# Main_MPPT.net
KiCad netlist of a schematic drawn in Altium Designer
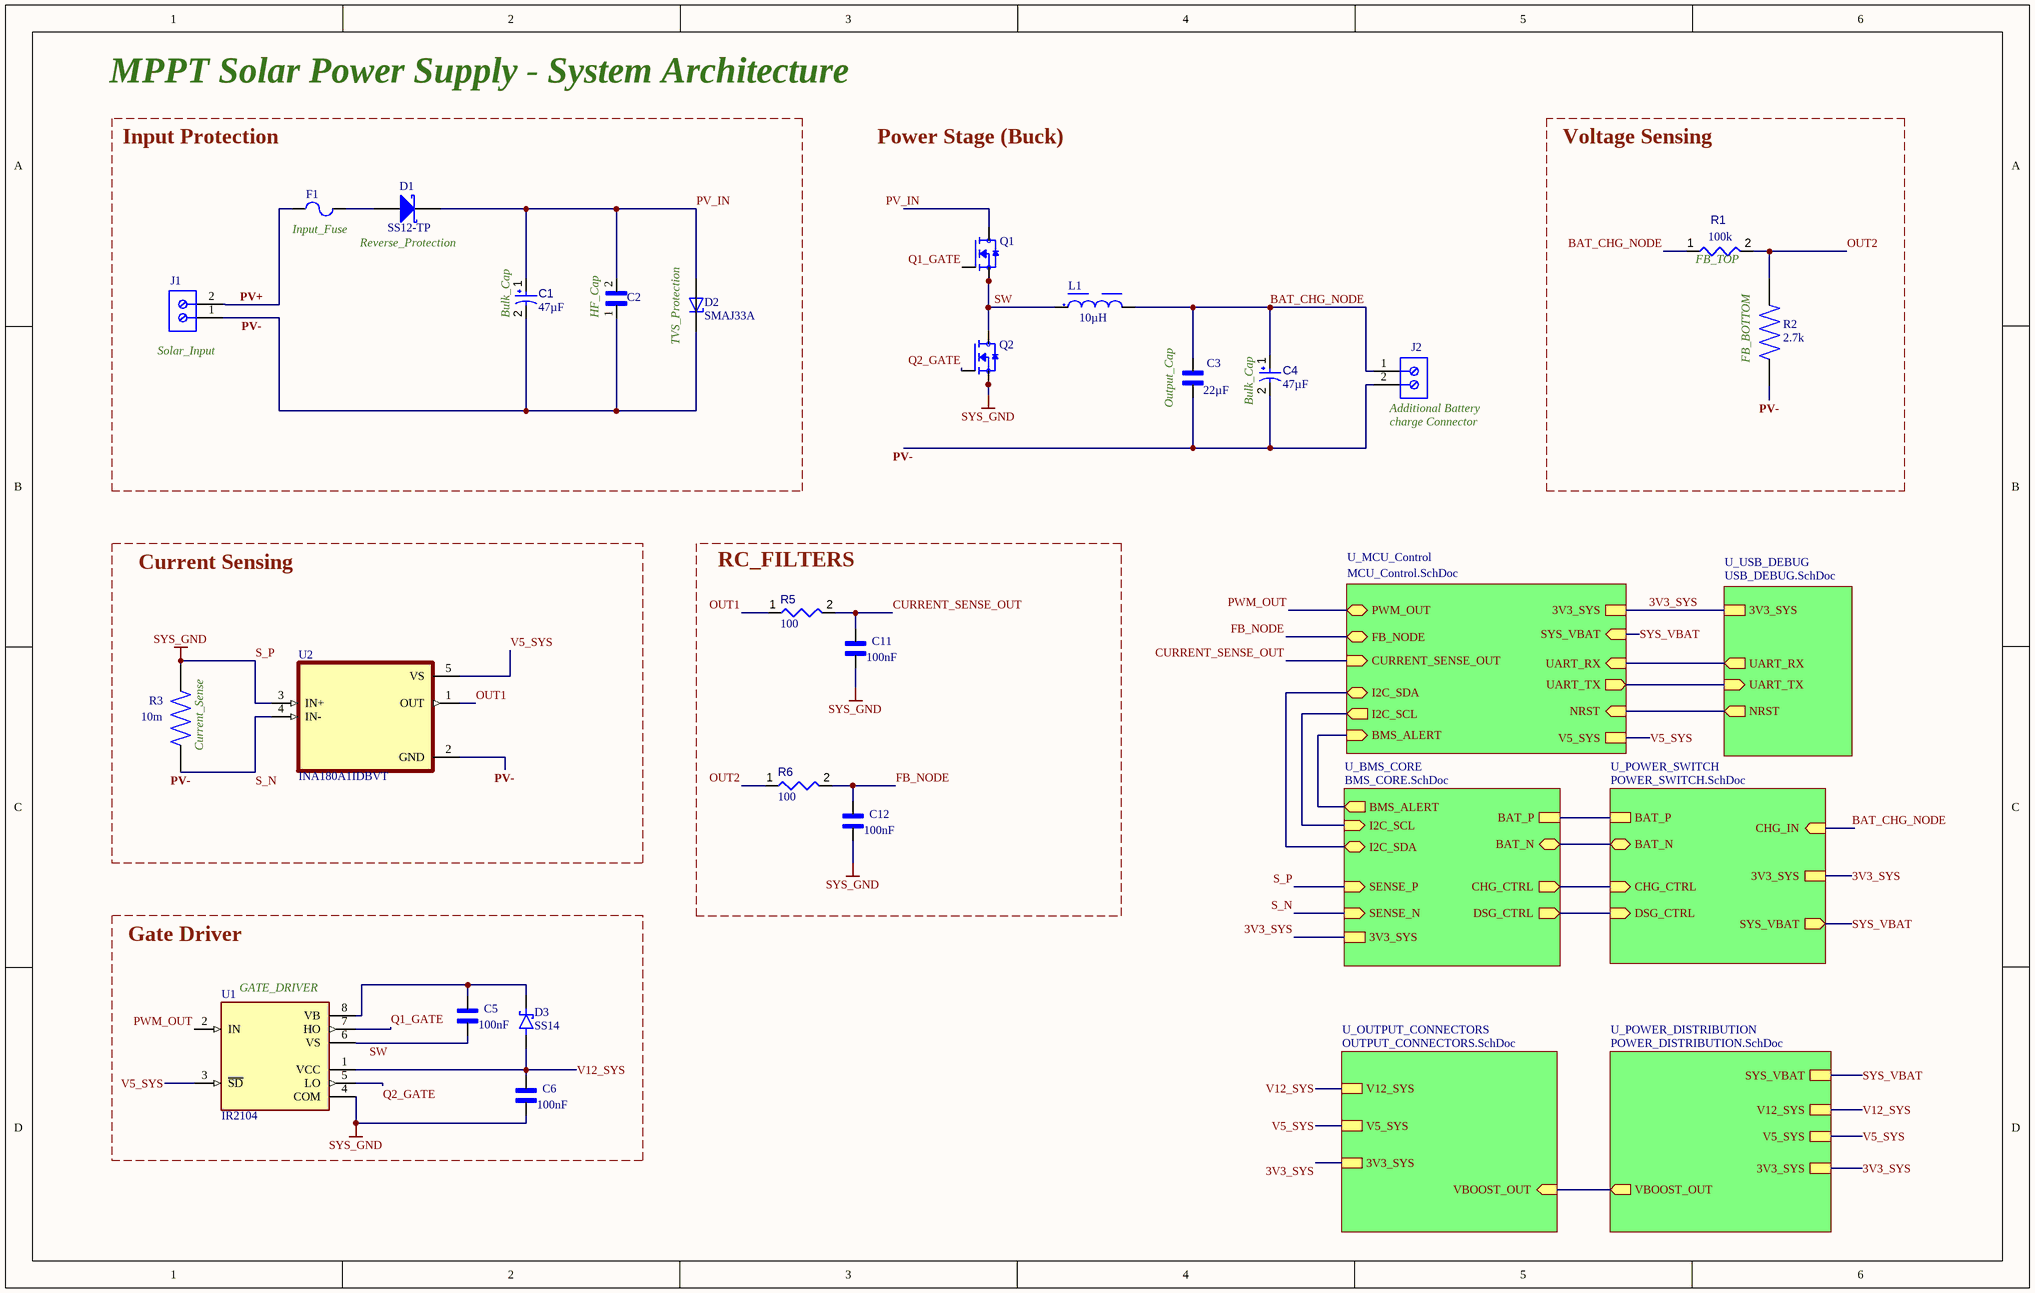
[diagram p0: Main_MPPT.SchDoc]

(export (version "E")
  (design (tool "Eeschema 10.0.6"))
  (components
    (comp (ref "C1")
      (value "47µF")
      (footprint "CAPPR55-250-1120X630X1220")
      (description "Aluminum Electrolytic Capacitor, 47 uF, +/- 20%, 50 V, -40 to 85 degC, 2-Pin THD, RoHS, Bulk")
      (fields (field (name "MANUFACTURER") "Panasonic") (field (name "TOLERANCE") "20%"))
      (libsource (lib "YUKESH S") (part "CAP-P-2"))
    )
    (comp (ref "C2")
      (value "C3216X7R1H106K160AE")
      (footprint "CAPC3216X190N")
      (description "10 ÂµF Â±10% 50V Ceramic Capacitor X7R 1206 (3216 Metric)")
      (fields (field (name "MF") "TDK Corporation"))
      (libsource (lib "C3216X7R1H106K160AE") (part "C3216X7R1H106K160AE"))
    )
    (comp (ref "C3")
      (value "22µF")
      (footprint "CAPC3225X270N")
      (description "SMD capacitor X7R(EIA) with capacitance 22uF Tol.10%. Rated voltage 25Vdc 125C")
      (fields (field (name "MP") "GRM32ER71E226KE15L") (field (name "MF") "Murata Electronics"))
      (libsource (lib "YUKESH S") (part "GRM32ER71E226KE15L"))
    )
    (comp (ref "C4")
      (value "47µF")
      (footprint "CAPPR55-250-1120X630X1220")
      (description "Aluminum Electrolytic Capacitor, 47 uF, +/- 20%, 50 V, -40 to 85 degC, 2-Pin THD, RoHS, Bulk")
      (fields (field (name "MANUFACTURER") "Panasonic") (field (name "TOLERANCE") "20%"))
      (libsource (lib "") (part "CAP-P-2_1"))
    )
    (comp (ref "C5")
      (value "100nF")
      (footprint "CAPC1608X90N")
      (description "Capacitor MLCC 0603 100nF 16V")
      (fields (field (name "MP") "0603YC104KAZ2A") (field (name "MF") "AVX"))
      (libsource (lib "YUKESH S") (part "0603YC104KAZ2A"))
    )
    (comp (ref "C6")
      (value "100nF")
      (footprint "CAPC1608X90N")
      (description "Capacitor MLCC 0603 100nF 16V")
      (fields (field (name "MP") "0603YC104KAZ2A") (field (name "MF") "AVX"))
      (libsource (lib "YUKESH S") (part "0603YC104KAZ2A"))
    )
    (comp (ref "C11")
      (value "100nF")
      (footprint "CAPC1608X90N")
      (description "Capacitor MLCC 0603 100nF 16V")
      (fields (field (name "MP") "0603YC104KAZ2A") (field (name "MF") "AVX"))
      (libsource (lib "YUKESH S") (part "0603YC104KAZ2A"))
    )
    (comp (ref "C12")
      (value "100nF")
      (footprint "CAPC1608X90N")
      (description "Capacitor MLCC 0603 100nF 16V")
      (fields (field (name "MP") "0603YC104KAZ2A") (field (name "MF") "AVX"))
      (libsource (lib "YUKESH S") (part "0603YC104KAZ2A"))
    )
    (comp (ref "D1")
      (value "SS12-TP")
      (footprint "MCC-DO-214AC-2_V")
      (description "Schottky Rectifier, 20 V, 1 A, -55 to 125 degC, 2-Pin DO-214AC, RoHS, Tape and Reel")
      (fields (field (name "MANUFACTURER") "Micro Commercial Components"))
      (libsource (lib "YUKESH S") (part "DSKY-AK-2"))
    )
    (comp (ref "D2")
      (value "SMAJ33A")
      (footprint "Copy of DIOM4325X250N")
      (description "400W, 38.7V, 5%, Unidirectional, TVS")
      (fields (field (name "MF") "Taiwan Semiconductor"))
      (libsource (lib "YUKESH S") (part "SMAJ33A"))
    )
    (comp (ref "D3")
      (value "SS14")
      (footprint "DIOM4325X250N")
      (description "1A, 40V, Schottky Rectifier")
      (fields (field (name "MF") "Taiwan Semiconductor"))
      (libsource (lib "YUKESH S") (part "SS14"))
    )
    (comp (ref "F1")
      (value "0154001.DR")
      (footprint "LFUS-0154001.DR_V")
      (description "Very Fast-Acting Fuse, 1 A, -55 to 125 degC, 2-Pin SMD, RoHS, Tape and Reel")
      (fields (field (name "MANUFACTURER") "Littelfuse"))
      (libsource (lib "Altium Content Vault") (part "FUSE-2"))
    )
    (comp (ref "J1")
      (value "691254810002")
      (footprint "691254810002")
      (description "Terminal Block, 10MM Pitch, Horizontal, Rising Cage Clamp, 12-30 AWG, 2 Pin")
      (libsource (lib "") (part "TBL - 1R - 02P - Screw_1"))
    )
    (comp (ref "J2")
      (value "691254810002")
      (footprint "691254810002")
      (description "Terminal Block, 10MM Pitch, Horizontal, Rising Cage Clamp, 12-30 AWG, 2 Pin")
      (libsource (lib "Altium Content Vault") (part "TBL - 1R - 02P - Screw"))
    )
    (comp (ref "L1")
      (value "10µH")
      (footprint "WE-PD_1260")
      (description "Power inductor SMD WE-PD L 10.0uH 4.09A")
      (fields (field (name "MF") "WÃ¼rth Elektronik") (field (name "MP") "74477110"))
      (libsource (lib "YUKESH S") (part "WE-PD_1260"))
    )
    (comp (ref "Q1")
      (value "CSD18540Q5BT")
      (footprint "TRANS_CSD18540Q5BT")
      (description "60-V, N channel NexFETâ„¢ power MOSFET, single SON 5 mm x 6 mm, 2.2 mOhm")
      (fields (field (name "MF") "Texas Instruments"))
      (libsource (lib "YUKESH S") (part "CSD18540Q5BT"))
    )
    (comp (ref "Q2")
      (value "CSD18540Q5BT")
      (footprint "TRANS_CSD18540Q5BT")
      (description "60-V, N channel NexFETâ„¢ power MOSFET, single SON 5 mm x 6 mm, 2.2 mOhm")
      (fields (field (name "MF") "Texas Instruments"))
      (libsource (lib "YUKESH S") (part "CSD18540Q5BT"))
    )
    (comp (ref "R1")
      (value "100k")
      (footprint "RESC0402(1005)_L")
      (description "100K 0.063W 1% 0402 (1005 Metric)  SMD")
      (fields (field (name "POWER") "63mW") (field (name "TOLERANCE") "1%"))
      (libsource (lib "YUKESH S") (part "100KR2F"))
    )
    (comp (ref "R2")
      (value "2.7k")
      (footprint "RES_ERJ2RHD2702X")
      (description "ERJ2R Resistor 0.063W 27K 0.5% 50ppm")
      (fields (field (name "MF") "Panasonic") (field (name "MP") "ERJ2RHD2702X"))
      (libsource (lib "YUKESH S") (part "ERJ2RHD2702X"))
    )
    (comp (ref "R3")
      (value "10m")
      (footprint "RESC6331X88N")
      (fields (field (name "MP") "WSL2512R0100FEA18") (field (name "MF") "Vishay Intertechnology"))
      (libsource (lib "YUKESH S") (part "WSL2512R0100FEA18"))
    )
    (comp (ref "R5")
      (value "100")
      (footprint "RESC0402(1005)_L")
      (description "100R 0.063W 1% 0402 (1005 Metric)  SMD")
      (fields (field (name "TOLERANCE") "1%") (field (name "POWER") "63mW"))
      (libsource (lib "YUKESH S") (part "100R2F"))
    )
    (comp (ref "R6")
      (value "100")
      (footprint "RESC0402(1005)_L")
      (description "100R 0.063W 1% 0402 (1005 Metric)  SMD")
      (fields (field (name "TOLERANCE") "1%") (field (name "POWER") "63mW"))
      (libsource (lib "YUKESH S") (part "100R2F"))
    )
    (comp (ref "U1")
      (value "IR2104")
      (footprint "DIP762W45P254L988H533Q8")
      (description "Half-Bridge Gate Driver IC Non-Inverting 8-PDIP")
      (fields (field (name "MF") "Infineon Technologies"))
      (libsource (lib "YUKESH S") (part "IR2104"))
    )
    (comp (ref "U2")
      (value "INA180A1IDBVT")
      (footprint "SOT95P280X145-5N")
      (description "26V, 350kHz ì „ë¥˜ ê°ì§€ ì")
      (fields (field (name "MF") "Texas Instruments"))
      (libsource (lib "YUKESH S") (part "INA180A1IDBVT"))
    )
  )
  (nets
    (net (code "2") (name "/BAT_CHG_NODE") (class "Default")
      (node (ref "C3") (pin "2") (pinfunction "2_2") (pintype "passive"))
      (node (ref "C4") (pin "1") (pinfunction "1_1") (pintype "passive"))
      (node (ref "J2") (pin "1") (pinfunction "1_1") (pintype "passive"))
      (node (ref "L1") (pin "2") (pinfunction "2_2") (pintype "passive"))
      (node (ref "R1") (pin "1") (pinfunction "1_1") (pintype "passive"))
    )
    (net (code "7") (name "/CURRENT_SENSE_OUT") (class "Default")
      (node (ref "C11") (pin "2") (pinfunction "2_2") (pintype "passive"))
      (node (ref "R5") (pin "2") (pinfunction "2_2") (pintype "passive"))
    )
    (net (code "9") (name "/FB_NODE") (class "Default")
      (node (ref "C12") (pin "2") (pinfunction "2_2") (pintype "passive"))
      (node (ref "R6") (pin "2") (pinfunction "2_2") (pintype "passive"))
    )
    (net (code "13") (name "/OUT1") (class "Default")
      (node (ref "R5") (pin "1") (pinfunction "1_1") (pintype "passive"))
      (node (ref "U2") (pin "1") (pinfunction "OUT_1") (pintype "output"))
    )
    (net (code "14") (name "/OUT2") (class "Default")
      (node (ref "R1") (pin "2") (pinfunction "2_2") (pintype "passive"))
      (node (ref "R2") (pin "2") (pinfunction "2_2") (pintype "passive"))
      (node (ref "R6") (pin "1") (pinfunction "1_1") (pintype "passive"))
    )
    (net (code "15") (name "/PV+") (class "Default")
      (node (ref "F1") (pin "1") (pinfunction "1_1") (pintype "passive"))
      (node (ref "J1") (pin "2") (pinfunction "2_2") (pintype "passive"))
    )
    (net (code "16") (name "/PV-") (class "Default")
      (node (ref "C1") (pin "2") (pinfunction "2_2") (pintype "passive"))
      (node (ref "C2") (pin "1") (pinfunction "1_1") (pintype "passive"))
      (node (ref "C3") (pin "1") (pinfunction "1_1") (pintype "passive"))
      (node (ref "C4") (pin "2") (pinfunction "2_2") (pintype "passive"))
      (node (ref "D2") (pin "C") (pinfunction "C_C") (pintype "passive"))
      (node (ref "J1") (pin "1") (pinfunction "1_1") (pintype "passive"))
      (node (ref "J2") (pin "2") (pinfunction "2_2") (pintype "passive"))
      (node (ref "R2") (pin "1") (pinfunction "1_1") (pintype "passive"))
      (node (ref "R3") (pin "1") (pinfunction "1_1") (pintype "passive"))
      (node (ref "U2") (pin "2") (pinfunction "GND_2") (pintype "power_in"))
      (node (ref "U2") (pin "4") (pinfunction "IN-_4") (pintype "input"))
    )
    (net (code "17") (name "/PV_IN") (class "Default")
      (node (ref "C1") (pin "1") (pinfunction "1_1") (pintype "passive"))
      (node (ref "C2") (pin "2") (pinfunction "2_2") (pintype "passive"))
      (node (ref "D1") (pin "2") (pinfunction "K_2") (pintype "passive"))
      (node (ref "D2") (pin "A") (pinfunction "A_A") (pintype "passive"))
      (node (ref "Q1") (pin "5_6_7_8") (pinfunction "D_5_6_7_8") (pintype "passive"))
    )
    (net (code "18") (name "/PWM_OUT") (class "Default")
      (node (ref "U1") (pin "2") (pinfunction "IN_2") (pintype "input"))
    )
    (net (code "19") (name "/Q1_GATE") (class "Default")
      (node (ref "Q1") (pin "4") (pinfunction "G_4") (pintype "passive"))
      (node (ref "U1") (pin "7") (pinfunction "HO_7") (pintype "output"))
    )
    (net (code "20") (name "/Q2_GATE") (class "Default")
      (node (ref "Q2") (pin "4") (pinfunction "G_4") (pintype "passive"))
      (node (ref "U1") (pin "5") (pinfunction "LO_5") (pintype "output"))
    )
    (net (code "21") (name "/SW") (class "Default")
      (node (ref "C5") (pin "1") (pinfunction "1_1") (pintype "passive"))
      (node (ref "L1") (pin "1") (pinfunction "1_1") (pintype "passive"))
      (node (ref "Q1") (pin "1") (pinfunction "S_1") (pintype "passive"))
      (node (ref "Q1") (pin "2") (pinfunction "S_2") (pintype "passive"))
      (node (ref "Q1") (pin "3") (pinfunction "S_3") (pintype "passive"))
      (node (ref "Q2") (pin "5_6_7_8") (pinfunction "D_5_6_7_8") (pintype "passive"))
      (node (ref "U1") (pin "6") (pinfunction "VS_6") (pintype "power_in"))
    )
    (net (code "25") (name "/V5_SYS") (class "Default")
      (node (ref "U1") (pin "3") (pinfunction "~{SD}_3") (pintype "input"))
      (node (ref "U2") (pin "5") (pinfunction "VS_5") (pintype "power_in"))
    )
    (net (code "26") (name "/V12_SYS") (class "Default")
      (node (ref "C6") (pin "2") (pinfunction "2_2") (pintype "passive"))
      (node (ref "D3") (pin "A") (pinfunction "A_A") (pintype "passive"))
      (node (ref "U1") (pin "1") (pinfunction "VCC_1") (pintype "power_in"))
    )
    (net (code "28") (name "Net-(D1-A)") (class "Default")
      (node (ref "D1") (pin "1") (pinfunction "A_1") (pintype "passive"))
      (node (ref "F1") (pin "2") (pinfunction "2_2") (pintype "passive"))
    )
    (net (code "29") (name "Net-(D3-K)") (class "Default")
      (node (ref "C5") (pin "2") (pinfunction "2_2") (pintype "passive"))
      (node (ref "D3") (pin "C") (pinfunction "K_C") (pintype "passive"))
      (node (ref "U1") (pin "8") (pinfunction "VB_8") (pintype "power_in"))
    )
    (net (code "30") (name "SYS_GND") (class "Default")
      (node (ref "C11") (pin "1") (pinfunction "1_1") (pintype "passive"))
      (node (ref "C12") (pin "1") (pinfunction "1_1") (pintype "passive"))
      (node (ref "C6") (pin "1") (pinfunction "1_1") (pintype "passive"))
      (node (ref "Q2") (pin "1") (pinfunction "S_1") (pintype "passive"))
      (node (ref "Q2") (pin "2") (pinfunction "S_2") (pintype "passive"))
      (node (ref "Q2") (pin "3") (pinfunction "S_3") (pintype "passive"))
      (node (ref "R3") (pin "2") (pinfunction "2_2") (pintype "passive"))
      (node (ref "U1") (pin "4") (pinfunction "COM_4") (pintype "power_in"))
      (node (ref "U2") (pin "3") (pinfunction "IN+_3") (pintype "input"))
    )
  )
)
